# Sheet2.net
KiCad netlist of a schematic drawn in Altium Designer
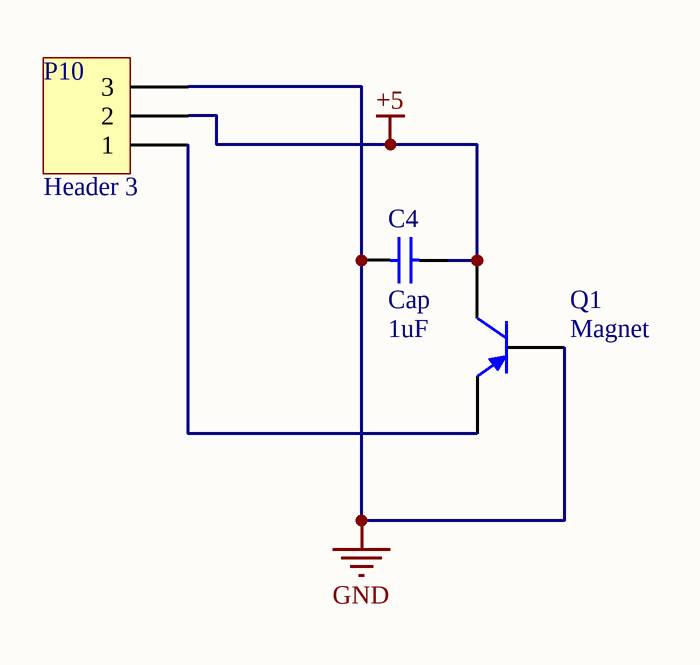
[diagram p0: Sheet2.SchDoc]

(export (version "E")
  (design (tool "Eeschema 10.0.6"))
  (components
    (comp (ref "C4")
      (value "Cap")
      (footprint "RAD-0.3")
      (description "Capacitor")
      (fields (field (name "ALTIUM_VALUE") "1uF") (field (name "PUBLISHER") "Altium Limited"))
      (libsource (lib "Miscellaneous Devices") (part "Cap"))
    )
    (comp (ref "P10")
      (value "Header 3")
      (footprint "HDR1X3")
      (description "Header, 3-Pin")
      (fields (field (name "PUBLISHER") "Altium Limited"))
      (libsource (lib "Miscellaneous Connectors") (part "Header 3"))
    )
    (comp (ref "Q1")
      (value "Magnet")
      (footprint "SOT-23B_N")
      (description "PNP Bipolar Transistor")
      (fields (field (name "PUBLISHER") "Altium Limited"))
      (libsource (lib "Miscellaneous Devices") (part "PNP"))
    )
  )
  (nets
    (net (code "1") (name "+5") (class "Default")
      (node (ref "C4") (pin "2") (pinfunction "2_2") (pintype "passive"))
      (node (ref "P10") (pin "2") (pinfunction "2_2") (pintype "passive"))
      (node (ref "Q1") (pin "1") (pinfunction "B_1") (pintype "passive"))
    )
    (net (code "2") (name "GND") (class "Default")
      (node (ref "C4") (pin "1") (pinfunction "1_1") (pintype "passive"))
      (node (ref "P10") (pin "3") (pinfunction "3_3") (pintype "passive"))
      (node (ref "Q1") (pin "2") (pinfunction "E_2") (pintype "passive"))
    )
    (net (code "3") (name "Net-(Q1-C)") (class "Default")
      (node (ref "P10") (pin "1") (pinfunction "1_1") (pintype "passive"))
      (node (ref "Q1") (pin "3") (pinfunction "C_3") (pintype "passive"))
    )
  )
)
